# OUTPUT_RELAY.net
KiCad netlist of a schematic drawn in Altium Designer
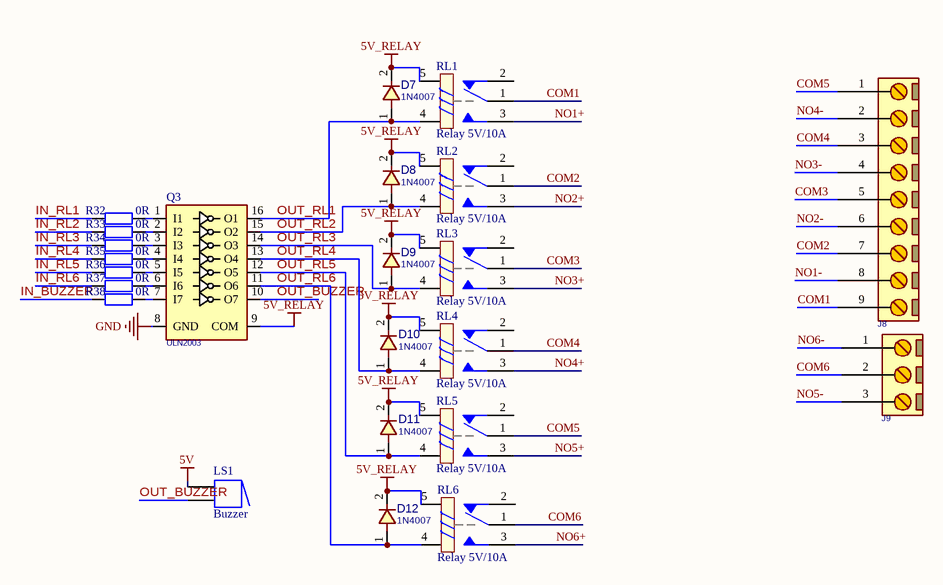
[diagram p0: OUTPUT_RELAY.SchDoc]

(export (version "E")
  (design (tool "Eeschema 10.0.6"))
  (components
    (comp (ref "D7")
      (value "1N4007")
      (footprint "D_SMA")
      (description "DIODE, GENERAL PURPOSE, 1000V/1A")
      (fields (field (name "MANF") "Kingtronics") (field (name "MANF_P#") "M7"))
      (libsource (lib "AH_Library") (part "DIODE_SMD_1N4007"))
    )
    (comp (ref "D8")
      (value "1N4007")
      (footprint "D_SMA")
      (description "DIODE, GENERAL PURPOSE, 1000V/1A")
      (fields (field (name "MANF") "Kingtronics") (field (name "MANF_P#") "M7"))
      (libsource (lib "AH_Library") (part "DIODE_SMD_1N4007"))
    )
    (comp (ref "D9")
      (value "1N4007")
      (footprint "D_SMA")
      (description "DIODE, GENERAL PURPOSE, 1000V/1A")
      (fields (field (name "MANF") "Kingtronics") (field (name "MANF_P#") "M7"))
      (libsource (lib "AH_Library") (part "DIODE_SMD_1N4007"))
    )
    (comp (ref "D10")
      (value "1N4007")
      (footprint "D_SMA")
      (description "DIODE, GENERAL PURPOSE, 1000V/1A")
      (fields (field (name "MANF") "Kingtronics") (field (name "MANF_P#") "M7"))
      (libsource (lib "AH_Library") (part "DIODE_SMD_1N4007"))
    )
    (comp (ref "D11")
      (value "1N4007")
      (footprint "D_SMA")
      (description "DIODE, GENERAL PURPOSE, 1000V/1A")
      (fields (field (name "MANF") "Kingtronics") (field (name "MANF_P#") "M7"))
      (libsource (lib "AH_Library") (part "DIODE_SMD_1N4007"))
    )
    (comp (ref "D12")
      (value "1N4007")
      (footprint "D_SMA")
      (description "DIODE, GENERAL PURPOSE, 1000V/1A")
      (fields (field (name "MANF") "Kingtronics") (field (name "MANF_P#") "M7"))
      (libsource (lib "AH_Library") (part "DIODE_SMD_1N4007"))
    )
    (comp (ref "J8")
      (value "CONN_TB9")
      (footprint "TBB_9")
      (description "CONN, TERMINAL BLOCK, 5.08mm pitch")
      (libsource (lib "AH_Library") (part "CONN_TB9"))
    )
    (comp (ref "J9")
      (value "CONN_TB3")
      (footprint "TBB_3")
      (description "CONN, TERMINAL BLOCK, 5.08mm pitch")
      (libsource (lib "AH_Library") (part "CONN_TB3"))
    )
    (comp (ref "LS1")
      (value "Buzzer")
      (footprint "Buzzer")
      (description "Magnetic Transducer Buzzer")
      (fields (field (name "PUBLISHER") "Altium Limited"))
      (libsource (lib "hphonglib") (part "Buzzer"))
    )
    (comp (ref "Q3")
      (value "ULN2003")
      (footprint "SO_16_W")
      (description "Darlington, 7-CH, 50V, 0.5A")
      (fields (field (name "MANF_P#") "ULN2003A") (field (name "MANF") "DIODES"))
      (libsource (lib "AH_Library") (part "ULN2003_SOP16"))
    )
    (comp (ref "R32")
      (value "0R_0603_1%")
      (footprint "tro smd 0603")
      (description "RES SMD 0603")
      (fields (field (name "MA_HANG") "0R"))
      (libsource (lib "THU VIEN SCH") (part "Tro 0603 5% 10k"))
    )
    (comp (ref "R33")
      (value "0R_0603_1%")
      (footprint "tro smd 0603")
      (description "RES SMD 0603")
      (fields (field (name "MA_HANG") "0R"))
      (libsource (lib "THU VIEN SCH") (part "Tro 0603 5% 10k"))
    )
    (comp (ref "R34")
      (value "0R_0603_1%")
      (footprint "tro smd 0603")
      (description "RES SMD 0603")
      (fields (field (name "MA_HANG") "0R"))
      (libsource (lib "THU VIEN SCH") (part "Tro 0603 5% 10k"))
    )
    (comp (ref "R35")
      (value "0R_0603_1%")
      (footprint "tro smd 0603")
      (description "RES SMD 0603")
      (fields (field (name "MA_HANG") "0R"))
      (libsource (lib "THU VIEN SCH") (part "Tro 0603 5% 10k"))
    )
    (comp (ref "R36")
      (value "0R_0603_1%")
      (footprint "tro smd 0603")
      (description "RES SMD 0603")
      (fields (field (name "MA_HANG") "0R"))
      (libsource (lib "THU VIEN SCH") (part "Tro 0603 5% 10k"))
    )
    (comp (ref "R37")
      (value "0R_0603_1%")
      (footprint "tro smd 0603")
      (description "RES SMD 0603")
      (fields (field (name "MA_HANG") "0R"))
      (libsource (lib "THU VIEN SCH") (part "Tro 0603 5% 10k"))
    )
    (comp (ref "R38")
      (value "0R_0603_1%")
      (footprint "tro smd 0603")
      (description "RES SMD 0603")
      (fields (field (name "MA_HANG") "0R"))
      (libsource (lib "THU VIEN SCH") (part "Tro 0603 5% 10k"))
    )
    (comp (ref "RL1")
      (value "Relay 5V/10A")
      (footprint "RL_10A_5V")
      (description "Relay SPDT,10A - 12VDC 5 Pin")
      (libsource (lib "lpson") (part "Relay 5V10A"))
    )
    (comp (ref "RL2")
      (value "Relay 5V/10A")
      (footprint "RL_10A_5V")
      (description "Relay SPDT,10A - 12VDC 5 Pin")
      (libsource (lib "lpson") (part "Relay 5V10A"))
    )
    (comp (ref "RL3")
      (value "Relay 5V/10A")
      (footprint "RL_10A_5V")
      (description "Relay SPDT,10A - 12VDC 5 Pin")
      (libsource (lib "lpson") (part "Relay 5V10A"))
    )
    (comp (ref "RL4")
      (value "Relay 5V/10A")
      (footprint "RL_10A_5V")
      (description "Relay SPDT,10A - 12VDC 5 Pin")
      (libsource (lib "lpson") (part "Relay 5V10A"))
    )
    (comp (ref "RL5")
      (value "Relay 5V/10A")
      (footprint "RL_10A_5V")
      (description "Relay SPDT,10A - 12VDC 5 Pin")
      (libsource (lib "lpson") (part "Relay 5V10A"))
    )
    (comp (ref "RL6")
      (value "Relay 5V/10A")
      (footprint "RL_10A_5V")
      (description "Relay SPDT,10A - 12VDC 5 Pin")
      (libsource (lib "lpson") (part "Relay 5V10A"))
    )
  )
  (nets
    (net (code "1") (name "/COM1") (class "Default")
      (node (ref "J8") (pin "9") (pinfunction "9_9") (pintype "passive"))
      (node (ref "RL1") (pin "1") (pinfunction "1_1") (pintype "passive"))
    )
    (net (code "2") (name "/COM2") (class "Default")
      (node (ref "J8") (pin "7") (pinfunction "7_7") (pintype "passive"))
      (node (ref "RL2") (pin "1") (pinfunction "1_1") (pintype "passive"))
    )
    (net (code "3") (name "/COM3") (class "Default")
      (node (ref "J8") (pin "5") (pinfunction "5_5") (pintype "passive"))
      (node (ref "RL3") (pin "1") (pinfunction "1_1") (pintype "passive"))
    )
    (net (code "4") (name "/COM4") (class "Default")
      (node (ref "J8") (pin "3") (pinfunction "3_3") (pintype "passive"))
      (node (ref "RL4") (pin "1") (pinfunction "1_1") (pintype "passive"))
    )
    (net (code "5") (name "/COM5") (class "Default")
      (node (ref "J8") (pin "1") (pinfunction "1_1") (pintype "passive"))
      (node (ref "RL5") (pin "1") (pinfunction "1_1") (pintype "passive"))
    )
    (net (code "6") (name "/COM6") (class "Default")
      (node (ref "J9") (pin "2") (pinfunction "2_2") (pintype "passive"))
      (node (ref "RL6") (pin "1") (pinfunction "1_1") (pintype "passive"))
    )
    (net (code "7") (name "/IN_BUZZER") (class "Default")
      (node (ref "R38") (pin "2") (pinfunction "2_2") (pintype "passive"))
    )
    (net (code "8") (name "/IN_RL1") (class "Default")
      (node (ref "R32") (pin "2") (pinfunction "2_2") (pintype "passive"))
    )
    (net (code "9") (name "/IN_RL2") (class "Default")
      (node (ref "R33") (pin "2") (pinfunction "2_2") (pintype "passive"))
    )
    (net (code "10") (name "/IN_RL3") (class "Default")
      (node (ref "R34") (pin "2") (pinfunction "2_2") (pintype "passive"))
    )
    (net (code "11") (name "/IN_RL4") (class "Default")
      (node (ref "R35") (pin "2") (pinfunction "2_2") (pintype "passive"))
    )
    (net (code "12") (name "/IN_RL5") (class "Default")
      (node (ref "R36") (pin "2") (pinfunction "2_2") (pintype "passive"))
    )
    (net (code "13") (name "/IN_RL6") (class "Default")
      (node (ref "R37") (pin "2") (pinfunction "2_2") (pintype "passive"))
    )
    (net (code "14") (name "/NO1+") (class "Default")
      (node (ref "RL1") (pin "3") (pinfunction "3_3") (pintype "passive"))
    )
    (net (code "15") (name "/NO1-") (class "Default")
      (node (ref "J8") (pin "8") (pinfunction "8_8") (pintype "passive"))
    )
    (net (code "16") (name "/NO2+") (class "Default")
      (node (ref "RL2") (pin "3") (pinfunction "3_3") (pintype "passive"))
    )
    (net (code "17") (name "/NO2-") (class "Default")
      (node (ref "J8") (pin "6") (pinfunction "6_6") (pintype "passive"))
    )
    (net (code "18") (name "/NO3+") (class "Default")
      (node (ref "RL3") (pin "3") (pinfunction "3_3") (pintype "passive"))
    )
    (net (code "19") (name "/NO3-") (class "Default")
      (node (ref "J8") (pin "4") (pinfunction "4_4") (pintype "passive"))
    )
    (net (code "20") (name "/NO4+") (class "Default")
      (node (ref "RL4") (pin "3") (pinfunction "3_3") (pintype "passive"))
    )
    (net (code "21") (name "/NO4-") (class "Default")
      (node (ref "J8") (pin "2") (pinfunction "2_2") (pintype "passive"))
    )
    (net (code "22") (name "/NO5+") (class "Default")
      (node (ref "RL5") (pin "3") (pinfunction "3_3") (pintype "passive"))
    )
    (net (code "23") (name "/NO5-") (class "Default")
      (node (ref "J9") (pin "3") (pinfunction "3_3") (pintype "passive"))
    )
    (net (code "24") (name "/NO6+") (class "Default")
      (node (ref "RL6") (pin "3") (pinfunction "3_3") (pintype "passive"))
    )
    (net (code "25") (name "/NO6-") (class "Default")
      (node (ref "J9") (pin "1") (pinfunction "1_1") (pintype "passive"))
    )
    (net (code "26") (name "/OUT_BUZZER") (class "Default")
      (node (ref "LS1") (pin "2") (pinfunction "2_2") (pintype "passive"))
      (node (ref "Q3") (pin "10") (pinfunction "O7_10") (pintype "passive"))
    )
    (net (code "27") (name "/OUT_RL1") (class "Default")
      (node (ref "D7") (pin "1") (pinfunction "1_1") (pintype "passive"))
      (node (ref "Q3") (pin "16") (pinfunction "O1_16") (pintype "passive"))
      (node (ref "RL1") (pin "4") (pinfunction "4_4") (pintype "passive"))
    )
    (net (code "28") (name "/OUT_RL2") (class "Default")
      (node (ref "D8") (pin "1") (pinfunction "1_1") (pintype "passive"))
      (node (ref "Q3") (pin "15") (pinfunction "O2_15") (pintype "passive"))
      (node (ref "RL2") (pin "4") (pinfunction "4_4") (pintype "passive"))
    )
    (net (code "29") (name "/OUT_RL3") (class "Default")
      (node (ref "D9") (pin "1") (pinfunction "1_1") (pintype "passive"))
      (node (ref "Q3") (pin "14") (pinfunction "O3_14") (pintype "passive"))
      (node (ref "RL3") (pin "4") (pinfunction "4_4") (pintype "passive"))
    )
    (net (code "30") (name "/OUT_RL4") (class "Default")
      (node (ref "D10") (pin "1") (pinfunction "1_1") (pintype "passive"))
      (node (ref "Q3") (pin "13") (pinfunction "O4_13") (pintype "passive"))
      (node (ref "RL4") (pin "4") (pinfunction "4_4") (pintype "passive"))
    )
    (net (code "31") (name "/OUT_RL5") (class "Default")
      (node (ref "D11") (pin "1") (pinfunction "1_1") (pintype "passive"))
      (node (ref "Q3") (pin "12") (pinfunction "O5_12") (pintype "passive"))
      (node (ref "RL5") (pin "4") (pinfunction "4_4") (pintype "passive"))
    )
    (net (code "32") (name "/OUT_RL6") (class "Default")
      (node (ref "D12") (pin "1") (pinfunction "1_1") (pintype "passive"))
      (node (ref "Q3") (pin "11") (pinfunction "O6_11") (pintype "passive"))
      (node (ref "RL6") (pin "4") (pinfunction "4_4") (pintype "passive"))
    )
    (net (code "33") (name "5V") (class "Default")
      (node (ref "LS1") (pin "1") (pinfunction "1_1") (pintype "passive"))
    )
    (net (code "34") (name "5V_RELAY") (class "Default")
      (node (ref "D10") (pin "2") (pinfunction "2_2") (pintype "passive"))
      (node (ref "D11") (pin "2") (pinfunction "2_2") (pintype "passive"))
      (node (ref "D12") (pin "2") (pinfunction "2_2") (pintype "passive"))
      (node (ref "D7") (pin "2") (pinfunction "2_2") (pintype "passive"))
      (node (ref "D8") (pin "2") (pinfunction "2_2") (pintype "passive"))
      (node (ref "D9") (pin "2") (pinfunction "2_2") (pintype "passive"))
      (node (ref "Q3") (pin "9") (pinfunction "COM_9") (pintype "passive"))
      (node (ref "RL1") (pin "5") (pinfunction "5_5") (pintype "passive"))
      (node (ref "RL2") (pin "5") (pinfunction "5_5") (pintype "passive"))
      (node (ref "RL3") (pin "5") (pinfunction "5_5") (pintype "passive"))
      (node (ref "RL4") (pin "5") (pinfunction "5_5") (pintype "passive"))
      (node (ref "RL5") (pin "5") (pinfunction "5_5") (pintype "passive"))
      (node (ref "RL6") (pin "5") (pinfunction "5_5") (pintype "passive"))
    )
    (net (code "35") (name "GND") (class "Default")
      (node (ref "Q3") (pin "8") (pinfunction "GND_8") (pintype "passive"))
    )
    (net (code "36") (name "Net-(Q3-I1)") (class "Default")
      (node (ref "Q3") (pin "1") (pinfunction "I1_1") (pintype "passive"))
      (node (ref "R32") (pin "1") (pinfunction "1_1") (pintype "passive"))
    )
    (net (code "37") (name "Net-(Q3-I2)") (class "Default")
      (node (ref "Q3") (pin "2") (pinfunction "I2_2") (pintype "passive"))
      (node (ref "R33") (pin "1") (pinfunction "1_1") (pintype "passive"))
    )
    (net (code "38") (name "Net-(Q3-I3)") (class "Default")
      (node (ref "Q3") (pin "3") (pinfunction "I3_3") (pintype "passive"))
      (node (ref "R34") (pin "1") (pinfunction "1_1") (pintype "passive"))
    )
    (net (code "39") (name "Net-(Q3-I4)") (class "Default")
      (node (ref "Q3") (pin "4") (pinfunction "I4_4") (pintype "passive"))
      (node (ref "R35") (pin "1") (pinfunction "1_1") (pintype "passive"))
    )
    (net (code "40") (name "Net-(Q3-I5)") (class "Default")
      (node (ref "Q3") (pin "5") (pinfunction "I5_5") (pintype "passive"))
      (node (ref "R36") (pin "1") (pinfunction "1_1") (pintype "passive"))
    )
    (net (code "41") (name "Net-(Q3-I6)") (class "Default")
      (node (ref "Q3") (pin "6") (pinfunction "I6_6") (pintype "passive"))
      (node (ref "R37") (pin "1") (pinfunction "1_1") (pintype "passive"))
    )
    (net (code "42") (name "Net-(Q3-I7)") (class "Default")
      (node (ref "Q3") (pin "7") (pinfunction "I7_7") (pintype "passive"))
      (node (ref "R38") (pin "1") (pinfunction "1_1") (pintype "passive"))
    )
    (net (code "43") (name "unconnected-(RL1-Pad2)") (class "Default")
      (node (ref "RL1") (pin "2") (pinfunction "2_2") (pintype "passive"))
    )
    (net (code "44") (name "unconnected-(RL2-Pad2)") (class "Default")
      (node (ref "RL2") (pin "2") (pinfunction "2_2") (pintype "passive"))
    )
    (net (code "45") (name "unconnected-(RL3-Pad2)") (class "Default")
      (node (ref "RL3") (pin "2") (pinfunction "2_2") (pintype "passive"))
    )
    (net (code "46") (name "unconnected-(RL4-Pad2)") (class "Default")
      (node (ref "RL4") (pin "2") (pinfunction "2_2") (pintype "passive"))
    )
    (net (code "47") (name "unconnected-(RL5-Pad2)") (class "Default")
      (node (ref "RL5") (pin "2") (pinfunction "2_2") (pintype "passive"))
    )
    (net (code "48") (name "unconnected-(RL6-Pad2)") (class "Default")
      (node (ref "RL6") (pin "2") (pinfunction "2_2") (pintype "passive"))
    )
  )
)
